# firstTestUno.net
KiCad netlist of a schematic drawn in EAGLE
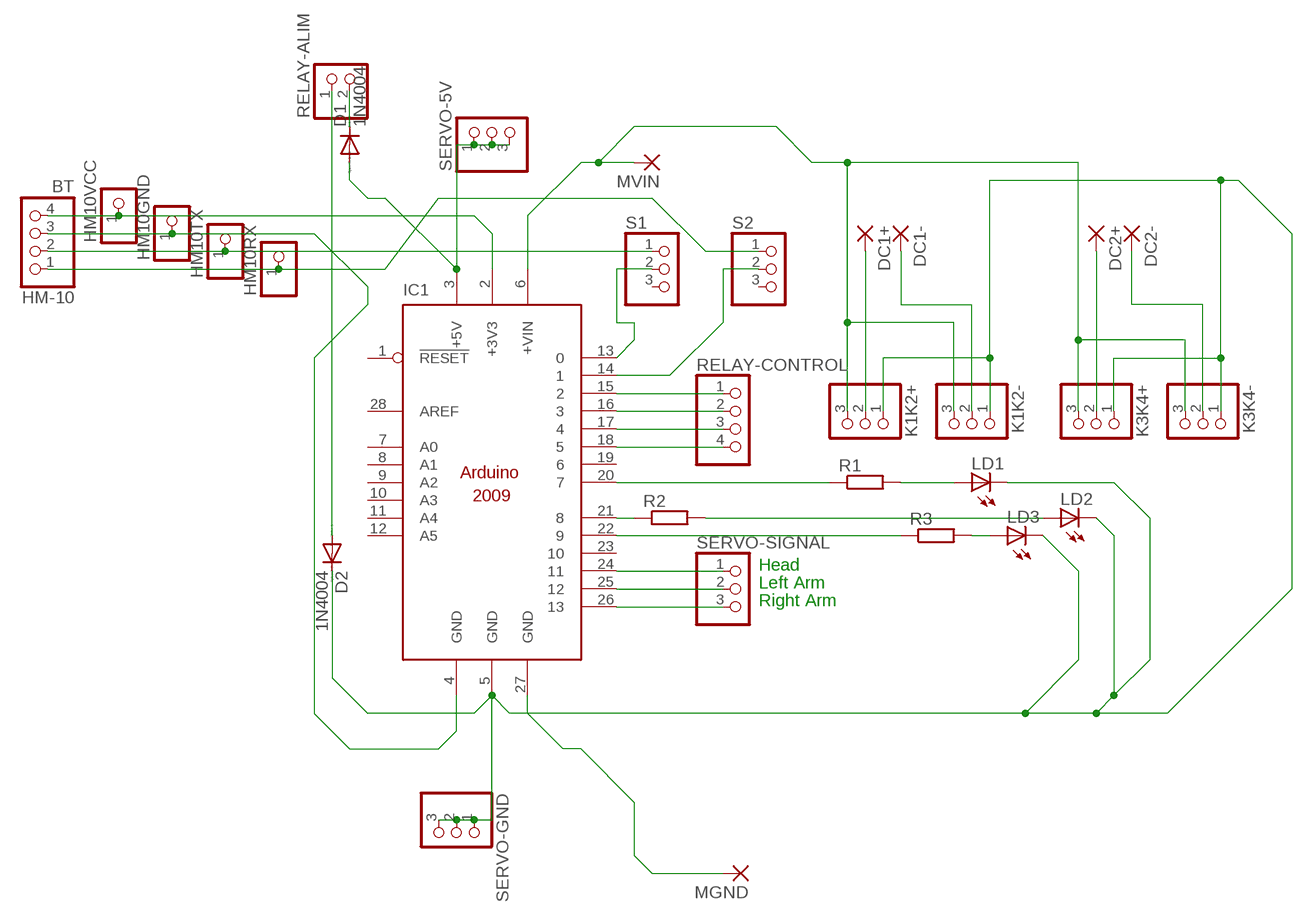
[diagram p0: schematic, sheet 1]

(export (version "E")
  (design (tool "Eeschema 10.0.6"))
  (components
    (comp (ref "D1")
      (value "1N4004")
      (footprint "eagle-import:DO41-10")
      (fields (field (name "MF") "MULTICOMP") (field (name "MPN") "1N4004+"))
      (libsource (lib "eagle-import") (part "1N4004"))
    )
    (comp (ref "D2")
      (value "1N4004")
      (footprint "eagle-import:DO41-10")
      (libsource (lib "eagle-import") (part "1N4004"))
    )
    (comp (ref "DC1+")
      (value "3,17/1,3")
      (footprint "eagle-import:3,17_1,3")
      (libsource (lib "eagle-import") (part "3,17/1,3"))
    )
    (comp (ref "DC1-")
      (value "3,17/1,3")
      (footprint "eagle-import:3,17_1,3")
      (libsource (lib "eagle-import") (part "3,17/1,3"))
    )
    (comp (ref "DC2+")
      (value "3,17/1,3")
      (footprint "eagle-import:3,17_1,3")
      (libsource (lib "eagle-import") (part "3,17/1,3"))
    )
    (comp (ref "DC2-")
      (value "3,17/1,3")
      (footprint "eagle-import:3,17_1,3")
      (libsource (lib "eagle-import") (part "3,17/1,3"))
    )
    (comp (ref "HM-10")
      (value "BT")
      (footprint "eagle-import:1X04")
      (libsource (lib "eagle-import") (part "PINHD-1X4"))
    )
    (comp (ref "HM10GND")
      (value "PINHD-1X1")
      (footprint "eagle-import:1X01")
      (libsource (lib "eagle-import") (part "PINHD-1X1"))
    )
    (comp (ref "HM10RX")
      (value "PINHD-1X1")
      (footprint "eagle-import:1X01")
      (libsource (lib "eagle-import") (part "PINHD-1X1"))
    )
    (comp (ref "HM10TX")
      (value "PINHD-1X1")
      (footprint "eagle-import:1X01")
      (libsource (lib "eagle-import") (part "PINHD-1X1"))
    )
    (comp (ref "HM10VCC")
      (value "PINHD-1X1")
      (footprint "eagle-import:1X01")
      (libsource (lib "eagle-import") (part "PINHD-1X1"))
    )
    (comp (ref "IC1")
      (value "ARDUINO2009_10")
      (footprint "eagle-import:ARDUINO2009")
      (libsource (lib "eagle-import") (part "ARDUINO2009_10"))
    )
    (comp (ref "K1K2+")
      (value "PINHD-1X3/90")
      (footprint "eagle-import:1X03_90")
      (libsource (lib "eagle-import") (part "PINHD-1X3/90"))
    )
    (comp (ref "K1K2-")
      (value "PINHD-1X3/90")
      (footprint "eagle-import:1X03_90")
      (libsource (lib "eagle-import") (part "PINHD-1X3/90"))
    )
    (comp (ref "K3K4+")
      (value "PINHD-1X3/90")
      (footprint "eagle-import:1X03_90")
      (libsource (lib "eagle-import") (part "PINHD-1X3/90"))
    )
    (comp (ref "K3K4-")
      (value "PINHD-1X3/90")
      (footprint "eagle-import:1X03_90")
      (libsource (lib "eagle-import") (part "PINHD-1X3/90"))
    )
    (comp (ref "LD1")
      (value "LED3MM")
      (footprint "eagle-import:LED3MM")
      (fields (field (name "MF") "MULTICOMP") (field (name "MPN") "LED 2F"))
      (libsource (lib "eagle-import") (part "LED3MM"))
    )
    (comp (ref "LD2")
      (value "LED3MM")
      (footprint "eagle-import:LED3MM")
      (fields (field (name "MF") "MULTICOMP") (field (name "MPN") "LED 2F"))
      (libsource (lib "eagle-import") (part "LED3MM"))
    )
    (comp (ref "LD3")
      (value "LED3MM")
      (footprint "eagle-import:LED3MM")
      (fields (field (name "MF") "MULTICOMP") (field (name "MPN") "LED 2F"))
      (libsource (lib "eagle-import") (part "LED3MM"))
    )
    (comp (ref "MGND")
      (value "3,17/1,3")
      (footprint "eagle-import:3,17_1,3")
      (libsource (lib "eagle-import") (part "3,17/1,3"))
    )
    (comp (ref "MVIN")
      (value "3,17/1,3")
      (footprint "eagle-import:3,17_1,3")
      (libsource (lib "eagle-import") (part "3,17/1,3"))
    )
    (comp (ref "R1")
      (value "R-EU_0207/10")
      (footprint "eagle-import:0207_10")
      (libsource (lib "eagle-import") (part "R-EU_0207/10"))
    )
    (comp (ref "R2")
      (value "R-EU_0207/10")
      (footprint "eagle-import:0207_10")
      (libsource (lib "eagle-import") (part "R-EU_0207/10"))
    )
    (comp (ref "R3")
      (value "R-EU_0207/10")
      (footprint "eagle-import:0207_10")
      (libsource (lib "eagle-import") (part "R-EU_0207/10"))
    )
    (comp (ref "RELAY-ALIM")
      (value "PINHD-1X2")
      (footprint "eagle-import:1X02")
      (fields (field (name "MF") "EPCOS") (field (name "MPN") "B65659F0001X023"))
      (libsource (lib "eagle-import") (part "PINHD-1X2"))
    )
    (comp (ref "RELAY-CONTROL")
      (value "PINHD-1X4")
      (footprint "eagle-import:1X04")
      (libsource (lib "eagle-import") (part "PINHD-1X4"))
    )
    (comp (ref "S1")
      (value "PINHD-1X3")
      (footprint "eagle-import:1X03")
      (libsource (lib "eagle-import") (part "PINHD-1X3"))
    )
    (comp (ref "S2")
      (value "PINHD-1X3")
      (footprint "eagle-import:1X03")
      (libsource (lib "eagle-import") (part "PINHD-1X3"))
    )
    (comp (ref "SERVO-5V")
      (value "PINHD-1X3")
      (footprint "eagle-import:1X03")
      (libsource (lib "eagle-import") (part "PINHD-1X3"))
    )
    (comp (ref "SERVO-GND")
      (value "PINHD-1X3")
      (footprint "eagle-import:1X03")
      (libsource (lib "eagle-import") (part "PINHD-1X3"))
    )
    (comp (ref "SERVO-SIGNAL")
      (value "PINHD-1X3")
      (footprint "eagle-import:1X03")
      (fields (field (name "MF") "TE CONNECTIVITY") (field (name "MPN") "V23234A0001X038-EV-144"))
      (libsource (lib "eagle-import") (part "PINHD-1X3"))
    )
  )
  (nets
    (net (code "1") (name "Net-(D1-PadC)") (class "Default")
      (node (ref "D1") (pin "C") (pinfunction "C_C") (pintype "passive"))
      (node (ref "RELAY-ALIM") (pin "2") (pinfunction "2_2") (pintype "passive"))
    )
    (net (code "2") (name "Net-(D2-PadA)") (class "Default")
      (node (ref "D2") (pin "A") (pinfunction "A_A") (pintype "passive"))
      (node (ref "RELAY-ALIM") (pin "1") (pinfunction "1_1") (pintype "passive"))
    )
    (net (code "3") (name "Net-(DC1+-P)") (class "Default")
      (node (ref "DC1+") (pin "1") (pinfunction "P_1") (pintype "passive"))
      (node (ref "K1K2+") (pin "2") (pinfunction "2_2") (pintype "passive"))
    )
    (net (code "4") (name "Net-(DC1--P)") (class "Default")
      (node (ref "DC1-") (pin "1") (pinfunction "P_1") (pintype "passive"))
      (node (ref "K1K2-") (pin "2") (pinfunction "2_2") (pintype "passive"))
    )
    (net (code "5") (name "Net-(DC2+-P)") (class "Default")
      (node (ref "DC2+") (pin "1") (pinfunction "P_1") (pintype "passive"))
      (node (ref "K3K4+") (pin "2") (pinfunction "2_2") (pintype "passive"))
    )
    (net (code "6") (name "Net-(DC2--P)") (class "Default")
      (node (ref "DC2-") (pin "1") (pinfunction "P_1") (pintype "passive"))
      (node (ref "K3K4-") (pin "2") (pinfunction "2_2") (pintype "passive"))
    )
    (net (code "7") (name "Net-(HM-10-Pad1)") (class "Default")
      (node (ref "HM-10") (pin "1") (pinfunction "1_1") (pintype "passive"))
      (node (ref "HM10RX") (pin "1") (pinfunction "1_1") (pintype "passive"))
      (node (ref "S2") (pin "1") (pinfunction "1_1") (pintype "passive"))
    )
    (net (code "8") (name "Net-(HM-10-Pad2)") (class "Default")
      (node (ref "HM-10") (pin "2") (pinfunction "2_2") (pintype "passive"))
      (node (ref "HM10TX") (pin "1") (pinfunction "1_1") (pintype "passive"))
      (node (ref "S1") (pin "1") (pinfunction "1_1") (pintype "passive"))
    )
    (net (code "9") (name "Net-(HM-10-Pad3)") (class "Default")
      (node (ref "HM-10") (pin "3") (pinfunction "3_3") (pintype "passive"))
      (node (ref "HM10GND") (pin "1") (pinfunction "1_1") (pintype "passive"))
      (node (ref "IC1") (pin "4") (pinfunction "GND_4") (pintype "power_in"))
    )
    (net (code "10") (name "Net-(IC1-+3V3)") (class "Default")
      (node (ref "HM-10") (pin "4") (pinfunction "4_4") (pintype "passive"))
      (node (ref "HM10VCC") (pin "1") (pinfunction "1_1") (pintype "passive"))
      (node (ref "IC1") (pin "2") (pinfunction "+3V3_2") (pintype "power_in"))
    )
    (net (code "11") (name "Net-(IC1-+5V)") (class "Default")
      (node (ref "D1") (pin "A") (pinfunction "A_A") (pintype "passive"))
      (node (ref "IC1") (pin "3") (pinfunction "+5V_3") (pintype "power_in"))
      (node (ref "SERVO-5V") (pin "1") (pinfunction "1_1") (pintype "passive"))
      (node (ref "SERVO-5V") (pin "2") (pinfunction "2_2") (pintype "passive"))
      (node (ref "SERVO-5V") (pin "3") (pinfunction "3_3") (pintype "passive"))
    )
    (net (code "12") (name "Net-(IC1-+VIN)") (class "Default")
      (node (ref "IC1") (pin "6") (pinfunction "+VIN_6") (pintype "bidirectional"))
      (node (ref "K1K2+") (pin "3") (pinfunction "3_3") (pintype "passive"))
      (node (ref "K1K2-") (pin "3") (pinfunction "3_3") (pintype "passive"))
      (node (ref "K3K4+") (pin "3") (pinfunction "3_3") (pintype "passive"))
      (node (ref "K3K4-") (pin "3") (pinfunction "3_3") (pintype "passive"))
      (node (ref "MVIN") (pin "1") (pinfunction "P_1") (pintype "passive"))
    )
    (net (code "13") (name "Net-(IC1-0)") (class "Default")
      (node (ref "IC1") (pin "13") (pinfunction "0_13") (pintype "bidirectional"))
      (node (ref "S1") (pin "2") (pinfunction "2_2") (pintype "passive"))
    )
    (net (code "14") (name "Net-(IC1-1)") (class "Default")
      (node (ref "IC1") (pin "14") (pinfunction "1_14") (pintype "bidirectional"))
      (node (ref "S2") (pin "2") (pinfunction "2_2") (pintype "passive"))
    )
    (net (code "15") (name "Net-(IC1-2)") (class "Default")
      (node (ref "IC1") (pin "15") (pinfunction "2_15") (pintype "bidirectional"))
      (node (ref "RELAY-CONTROL") (pin "1") (pinfunction "1_1") (pintype "passive"))
    )
    (net (code "16") (name "Net-(IC1-3)") (class "Default")
      (node (ref "IC1") (pin "16") (pinfunction "3_16") (pintype "bidirectional"))
      (node (ref "RELAY-CONTROL") (pin "2") (pinfunction "2_2") (pintype "passive"))
    )
    (net (code "17") (name "Net-(IC1-4)") (class "Default")
      (node (ref "IC1") (pin "17") (pinfunction "4_17") (pintype "bidirectional"))
      (node (ref "RELAY-CONTROL") (pin "3") (pinfunction "3_3") (pintype "passive"))
    )
    (net (code "18") (name "Net-(IC1-5)") (class "Default")
      (node (ref "IC1") (pin "18") (pinfunction "5_18") (pintype "bidirectional"))
      (node (ref "RELAY-CONTROL") (pin "4") (pinfunction "4_4") (pintype "passive"))
    )
    (net (code "19") (name "Net-(IC1-7)") (class "Default")
      (node (ref "IC1") (pin "20") (pinfunction "7_20") (pintype "bidirectional"))
      (node (ref "R1") (pin "1") (pinfunction "1_1") (pintype "passive"))
    )
    (net (code "20") (name "Net-(IC1-8)") (class "Default")
      (node (ref "IC1") (pin "21") (pinfunction "8_21") (pintype "bidirectional"))
      (node (ref "R2") (pin "1") (pinfunction "1_1") (pintype "passive"))
    )
    (net (code "21") (name "Net-(IC1-9)") (class "Default")
      (node (ref "IC1") (pin "22") (pinfunction "9_22") (pintype "bidirectional"))
      (node (ref "R3") (pin "1") (pinfunction "1_1") (pintype "passive"))
    )
    (net (code "22") (name "Net-(IC1-11)") (class "Default")
      (node (ref "IC1") (pin "24") (pinfunction "11_24") (pintype "bidirectional"))
      (node (ref "SERVO-SIGNAL") (pin "1") (pinfunction "1_1") (pintype "passive"))
    )
    (net (code "23") (name "Net-(IC1-12)") (class "Default")
      (node (ref "IC1") (pin "25") (pinfunction "12_25") (pintype "bidirectional"))
      (node (ref "SERVO-SIGNAL") (pin "2") (pinfunction "2_2") (pintype "passive"))
    )
    (net (code "24") (name "Net-(IC1-13)") (class "Default")
      (node (ref "IC1") (pin "26") (pinfunction "13_26") (pintype "bidirectional"))
      (node (ref "SERVO-SIGNAL") (pin "3") (pinfunction "3_3") (pintype "passive"))
    )
    (net (code "25") (name "Net-(LD1-C)") (class "Default")
      (node (ref "D2") (pin "C") (pinfunction "C_C") (pintype "passive"))
      (node (ref "IC1") (pin "5") (pinfunction "GND_5") (pintype "power_in"))
      (node (ref "K1K2+") (pin "1") (pinfunction "1_1") (pintype "passive"))
      (node (ref "K1K2-") (pin "1") (pinfunction "1_1") (pintype "passive"))
      (node (ref "K3K4+") (pin "1") (pinfunction "1_1") (pintype "passive"))
      (node (ref "K3K4-") (pin "1") (pinfunction "1_1") (pintype "passive"))
      (node (ref "LD1") (pin "K") (pinfunction "C_K") (pintype "passive"))
      (node (ref "LD2") (pin "K") (pinfunction "C_K") (pintype "passive"))
      (node (ref "LD3") (pin "K") (pinfunction "C_K") (pintype "passive"))
      (node (ref "SERVO-GND") (pin "1") (pinfunction "1_1") (pintype "passive"))
      (node (ref "SERVO-GND") (pin "2") (pinfunction "2_2") (pintype "passive"))
      (node (ref "SERVO-GND") (pin "3") (pinfunction "3_3") (pintype "passive"))
    )
    (net (code "26") (name "Net-(LD1-PadA)") (class "Default")
      (node (ref "LD1") (pin "A") (pinfunction "A_A") (pintype "passive"))
      (node (ref "R1") (pin "2") (pinfunction "2_2") (pintype "passive"))
    )
    (net (code "27") (name "Net-(LD2-PadA)") (class "Default")
      (node (ref "LD2") (pin "A") (pinfunction "A_A") (pintype "passive"))
      (node (ref "R2") (pin "2") (pinfunction "2_2") (pintype "passive"))
    )
    (net (code "28") (name "Net-(LD3-PadA)") (class "Default")
      (node (ref "LD3") (pin "A") (pinfunction "A_A") (pintype "passive"))
      (node (ref "R3") (pin "2") (pinfunction "2_2") (pintype "passive"))
    )
    (net (code "29") (name "Net-(MGND-P)") (class "Default")
      (node (ref "IC1") (pin "27") (pinfunction "GND_27") (pintype "power_in"))
      (node (ref "MGND") (pin "1") (pinfunction "P_1") (pintype "passive"))
    )
    (net (code "30") (name "unconnected-(IC1-6-Pad19)") (class "Default")
      (node (ref "IC1") (pin "19") (pinfunction "6_19") (pintype "bidirectional"))
    )
    (net (code "31") (name "unconnected-(IC1-10-Pad23)") (class "Default")
      (node (ref "IC1") (pin "23") (pinfunction "10_23") (pintype "bidirectional"))
    )
    (net (code "32") (name "unconnected-(IC1-A0-Pad7)") (class "Default")
      (node (ref "IC1") (pin "7") (pinfunction "A0_7") (pintype "bidirectional"))
    )
    (net (code "33") (name "unconnected-(IC1-A1-Pad8)") (class "Default")
      (node (ref "IC1") (pin "8") (pinfunction "A1_8") (pintype "bidirectional"))
    )
    (net (code "34") (name "unconnected-(IC1-A2-Pad9)") (class "Default")
      (node (ref "IC1") (pin "9") (pinfunction "A2_9") (pintype "bidirectional"))
    )
    (net (code "35") (name "unconnected-(IC1-A3-Pad10)") (class "Default")
      (node (ref "IC1") (pin "10") (pinfunction "A3_10") (pintype "bidirectional"))
    )
    (net (code "36") (name "unconnected-(IC1-A4-Pad11)") (class "Default")
      (node (ref "IC1") (pin "11") (pinfunction "A4_11") (pintype "bidirectional"))
    )
    (net (code "37") (name "unconnected-(IC1-A5-Pad12)") (class "Default")
      (node (ref "IC1") (pin "12") (pinfunction "A5_12") (pintype "bidirectional"))
    )
    (net (code "38") (name "unconnected-(IC1-AREF-Pad28)") (class "Default")
      (node (ref "IC1") (pin "28") (pinfunction "AREF_28") (pintype "bidirectional"))
    )
    (net (code "39") (name "unconnected-(IC1-~{RESET}-Pad1)") (class "Default")
      (node (ref "IC1") (pin "1") (pinfunction "~{RESET}_1") (pintype "bidirectional"))
    )
    (net (code "40") (name "unconnected-(S1-Pad3)") (class "Default")
      (node (ref "S1") (pin "3") (pinfunction "3_3") (pintype "passive"))
    )
    (net (code "41") (name "unconnected-(S2-Pad3)") (class "Default")
      (node (ref "S2") (pin "3") (pinfunction "3_3") (pintype "passive"))
    )
  )
)
